# a22.net
KiCad netlist of a schematic drawn in EAGLE
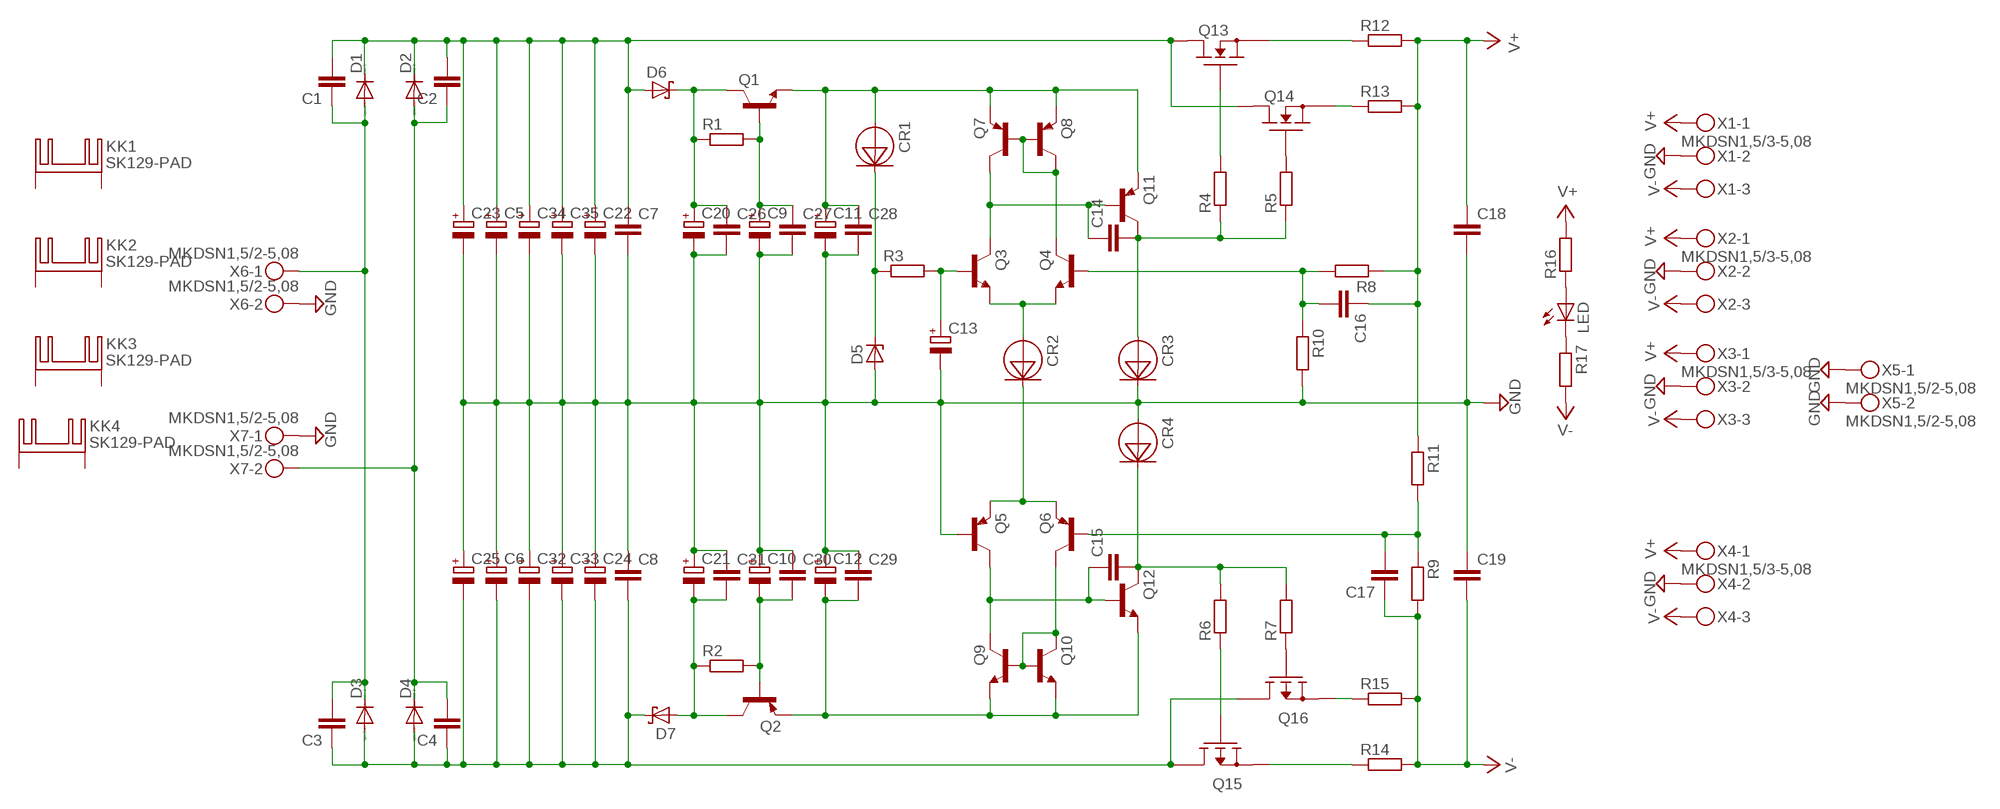
[diagram p0: schematic, sheet 1]

(export (version "E")
  (design (tool "Eeschema 10.0.6"))
  (components
    (comp (ref "C1")
      (value "C-EU025_050-025X075")
      (footprint "eagle-import:C025_050-025X075")
      (libsource (lib "eagle-import") (part "C-EU025_050-025X075"))
    )
    (comp (ref "C2")
      (value "C-EU025_050-025X075")
      (footprint "eagle-import:C025_050-025X075")
      (libsource (lib "eagle-import") (part "C-EU025_050-025X075"))
    )
    (comp (ref "C3")
      (value "C-EU025_050-025X075")
      (footprint "eagle-import:C025_050-025X075")
      (libsource (lib "eagle-import") (part "C-EU025_050-025X075"))
    )
    (comp (ref "C4")
      (value "C-EU025_050-025X075")
      (footprint "eagle-import:C025_050-025X075")
      (libsource (lib "eagle-import") (part "C-EU025_050-025X075"))
    )
    (comp (ref "C5")
      (value "CPOL-EUE10-30")
      (footprint "eagle-import:EB30D")
      (libsource (lib "eagle-import") (part "CPOL-EUE10-30"))
    )
    (comp (ref "C6")
      (value "CPOL-EUE10-30")
      (footprint "eagle-import:EB30D")
      (libsource (lib "eagle-import") (part "CPOL-EUE10-30"))
    )
    (comp (ref "C7")
      (value "C-EU050-075X075")
      (footprint "eagle-import:C050-075X075")
      (libsource (lib "eagle-import") (part "C-EU050-075X075"))
    )
    (comp (ref "C8")
      (value "C-EU050-075X075")
      (footprint "eagle-import:C050-075X075")
      (libsource (lib "eagle-import") (part "C-EU050-075X075"))
    )
    (comp (ref "C9")
      (value "CPOL-EUE5-10.5")
      (footprint "eagle-import:E5-10,5")
      (libsource (lib "eagle-import") (part "CPOL-EUE5-10.5"))
    )
    (comp (ref "C10")
      (value "CPOL-EUE5-10.5")
      (footprint "eagle-import:E5-10,5")
      (libsource (lib "eagle-import") (part "CPOL-EUE5-10.5"))
    )
    (comp (ref "C11")
      (value "CPOL-EUE5-13")
      (footprint "eagle-import:E5-13")
      (libsource (lib "eagle-import") (part "CPOL-EUE5-13"))
    )
    (comp (ref "C12")
      (value "CPOL-EUE5-13")
      (footprint "eagle-import:E5-13")
      (libsource (lib "eagle-import") (part "CPOL-EUE5-13"))
    )
    (comp (ref "C13")
      (value "CPOL-EUE5-10.5")
      (footprint "eagle-import:E5-10,5")
      (libsource (lib "eagle-import") (part "CPOL-EUE5-10.5"))
    )
    (comp (ref "C14")
      (value "C-EU050-075X075")
      (footprint "eagle-import:C050-075X075")
      (libsource (lib "eagle-import") (part "C-EU050-075X075"))
    )
    (comp (ref "C15")
      (value "C-EU050-075X075")
      (footprint "eagle-import:C050-075X075")
      (libsource (lib "eagle-import") (part "C-EU050-075X075"))
    )
    (comp (ref "C16")
      (value "C-EU025_050-045X075")
      (footprint "eagle-import:C025_050-045X075")
      (libsource (lib "eagle-import") (part "C-EU025_050-045X075"))
    )
    (comp (ref "C17")
      (value "C-EU025_050-045X075")
      (footprint "eagle-import:C025_050-045X075")
      (libsource (lib "eagle-import") (part "C-EU025_050-045X075"))
    )
    (comp (ref "C18")
      (value "C-EU050-075X075")
      (footprint "eagle-import:C050-075X075")
      (libsource (lib "eagle-import") (part "C-EU050-075X075"))
    )
    (comp (ref "C19")
      (value "C-EU050-075X075")
      (footprint "eagle-import:C050-075X075")
      (libsource (lib "eagle-import") (part "C-EU050-075X075"))
    )
    (comp (ref "C20")
      (value "CPOL-EUE5-10.5")
      (footprint "eagle-import:E5-10,5")
      (libsource (lib "eagle-import") (part "CPOL-EUE5-10.5"))
    )
    (comp (ref "C21")
      (value "CPOL-EUE5-10.5")
      (footprint "eagle-import:E5-10,5")
      (libsource (lib "eagle-import") (part "CPOL-EUE5-10.5"))
    )
    (comp (ref "C22")
      (value "CPOL-EUE7.5-18")
      (footprint "eagle-import:E7,5-18")
      (libsource (lib "eagle-import") (part "CPOL-EUE7.5-18"))
    )
    (comp (ref "C23")
      (value "CPOL-EUE7.5-18")
      (footprint "eagle-import:E7,5-18")
      (libsource (lib "eagle-import") (part "CPOL-EUE7.5-18"))
    )
    (comp (ref "C24")
      (value "CPOL-EUE7.5-18")
      (footprint "eagle-import:E7,5-18")
      (libsource (lib "eagle-import") (part "CPOL-EUE7.5-18"))
    )
    (comp (ref "C25")
      (value "CPOL-EUE7.5-18")
      (footprint "eagle-import:E7,5-18")
      (libsource (lib "eagle-import") (part "CPOL-EUE7.5-18"))
    )
    (comp (ref "C26")
      (value "C-EU050-035X075")
      (footprint "eagle-import:C050-035X075")
      (libsource (lib "eagle-import") (part "C-EU050-035X075"))
    )
    (comp (ref "C27")
      (value "C-EU050-035X075")
      (footprint "eagle-import:C050-035X075")
      (libsource (lib "eagle-import") (part "C-EU050-035X075"))
    )
    (comp (ref "C28")
      (value "C-EU050-035X075")
      (footprint "eagle-import:C050-035X075")
      (libsource (lib "eagle-import") (part "C-EU050-035X075"))
    )
    (comp (ref "C29")
      (value "C-EU050-035X075")
      (footprint "eagle-import:C050-035X075")
      (libsource (lib "eagle-import") (part "C-EU050-035X075"))
    )
    (comp (ref "C30")
      (value "C-EU050-035X075")
      (footprint "eagle-import:C050-035X075")
      (libsource (lib "eagle-import") (part "C-EU050-035X075"))
    )
    (comp (ref "C31")
      (value "C-EU050-035X075")
      (footprint "eagle-import:C050-035X075")
      (libsource (lib "eagle-import") (part "C-EU050-035X075"))
    )
    (comp (ref "C32")
      (value "CPOL-EUE7.5-18")
      (footprint "eagle-import:E7,5-18")
      (libsource (lib "eagle-import") (part "CPOL-EUE7.5-18"))
    )
    (comp (ref "C33")
      (value "CPOL-EUE7.5-18")
      (footprint "eagle-import:E7,5-18")
      (libsource (lib "eagle-import") (part "CPOL-EUE7.5-18"))
    )
    (comp (ref "C34")
      (value "CPOL-EUE7.5-18")
      (footprint "eagle-import:E7,5-18")
      (libsource (lib "eagle-import") (part "CPOL-EUE7.5-18"))
    )
    (comp (ref "C35")
      (value "CPOL-EUE7.5-18")
      (footprint "eagle-import:E7,5-18")
      (libsource (lib "eagle-import") (part "CPOL-EUE7.5-18"))
    )
    (comp (ref "CR1")
      (value "E-202")
      (footprint "eagle-import:DO-35-3")
      (libsource (lib "eagle-import") (part "E-202"))
    )
    (comp (ref "CR2")
      (value "E-202")
      (footprint "eagle-import:DO-35-3")
      (libsource (lib "eagle-import") (part "E-202"))
    )
    (comp (ref "CR3")
      (value "E-202")
      (footprint "eagle-import:DO-35-3")
      (libsource (lib "eagle-import") (part "E-202"))
    )
    (comp (ref "CR4")
      (value "E-202")
      (footprint "eagle-import:DO-35-3")
      (libsource (lib "eagle-import") (part "E-202"))
    )
    (comp (ref "D1")
      (value "MUR810")
      (footprint "eagle-import:TO220ACS")
      (libsource (lib "eagle-import") (part "MUR810"))
    )
    (comp (ref "D2")
      (value "MUR810")
      (footprint "eagle-import:TO220ACS")
      (libsource (lib "eagle-import") (part "MUR810"))
    )
    (comp (ref "D3")
      (value "MUR810")
      (footprint "eagle-import:TO220ACS")
      (libsource (lib "eagle-import") (part "MUR810"))
    )
    (comp (ref "D4")
      (value "MUR810")
      (footprint "eagle-import:TO220ACS")
      (libsource (lib "eagle-import") (part "MUR810"))
    )
    (comp (ref "D5")
      (value "BZX90")
      (footprint "eagle-import:DO34Z7")
      (libsource (lib "eagle-import") (part "BZX90"))
    )
    (comp (ref "D6")
      (value "1N5819-B")
      (footprint "eagle-import:DO41-7.6")
      (libsource (lib "eagle-import") (part "1N5819-B"))
    )
    (comp (ref "D7")
      (value "1N5819-B")
      (footprint "eagle-import:DO41-7.6")
      (libsource (lib "eagle-import") (part "1N5819-B"))
    )
    (comp (ref "KK1")
      (value "SK129-PAD")
      (footprint "eagle-import:SK129")
      (libsource (lib "eagle-import") (part "SK129-PAD"))
    )
    (comp (ref "KK2")
      (value "SK129-PAD")
      (footprint "eagle-import:SK129")
      (libsource (lib "eagle-import") (part "SK129-PAD"))
    )
    (comp (ref "KK3")
      (value "SK129-PAD")
      (footprint "eagle-import:SK129")
      (libsource (lib "eagle-import") (part "SK129-PAD"))
    )
    (comp (ref "KK4")
      (value "SK129-PAD")
      (footprint "eagle-import:SK129")
      (libsource (lib "eagle-import") (part "SK129-PAD"))
    )
    (comp (ref "LED")
      (value "LED5MM")
      (footprint "eagle-import:LED5MM")
      (libsource (lib "eagle-import") (part "LED5MM"))
    )
    (comp (ref "Q1")
      (value "BC550B")
      (footprint "eagle-import:TO92-EBC")
      (libsource (lib "eagle-import") (part "BC550B"))
    )
    (comp (ref "Q2")
      (value "BC560C")
      (footprint "eagle-import:TO92-EBC")
      (libsource (lib "eagle-import") (part "BC560C"))
    )
    (comp (ref "Q3")
      (value "BC550B")
      (footprint "eagle-import:TO92-EBC")
      (libsource (lib "eagle-import") (part "BC550B"))
    )
    (comp (ref "Q4")
      (value "BC550B")
      (footprint "eagle-import:TO92-EBC")
      (libsource (lib "eagle-import") (part "BC550B"))
    )
    (comp (ref "Q5")
      (value "BC560C")
      (footprint "eagle-import:TO92-EBC")
      (libsource (lib "eagle-import") (part "BC560C"))
    )
    (comp (ref "Q6")
      (value "BC560C")
      (footprint "eagle-import:TO92-EBC")
      (libsource (lib "eagle-import") (part "BC560C"))
    )
    (comp (ref "Q7")
      (value "BC560C")
      (footprint "eagle-import:TO92-EBC")
      (libsource (lib "eagle-import") (part "BC560C"))
    )
    (comp (ref "Q8")
      (value "BC560C")
      (footprint "eagle-import:TO92-EBC")
      (libsource (lib "eagle-import") (part "BC560C"))
    )
    (comp (ref "Q9")
      (value "BC550B")
      (footprint "eagle-import:TO92-EBC")
      (libsource (lib "eagle-import") (part "BC550B"))
    )
    (comp (ref "Q10")
      (value "BC550B")
      (footprint "eagle-import:TO92-EBC")
      (libsource (lib "eagle-import") (part "BC550B"))
    )
    (comp (ref "Q11")
      (value "BC560C")
      (footprint "eagle-import:TO92-EBC")
      (libsource (lib "eagle-import") (part "BC560C"))
    )
    (comp (ref "Q12")
      (value "BC550B")
      (footprint "eagle-import:TO92-EBC")
      (libsource (lib "eagle-import") (part "BC550B"))
    )
    (comp (ref "Q13")
      (value "IRFZ24N")
      (footprint "eagle-import:TO220V")
      (libsource (lib "eagle-import") (part "IRFZ24N"))
    )
    (comp (ref "Q14")
      (value "IRFZ24N")
      (footprint "eagle-import:TO220V")
      (libsource (lib "eagle-import") (part "IRFZ24N"))
    )
    (comp (ref "Q15")
      (value "IRF9Z34N")
      (footprint "eagle-import:TO220V")
      (libsource (lib "eagle-import") (part "IRF9Z34N"))
    )
    (comp (ref "Q16")
      (value "IRF9Z34N")
      (footprint "eagle-import:TO220V")
      (libsource (lib "eagle-import") (part "IRF9Z34N"))
    )
    (comp (ref "R1")
      (value "R-EU_0309/10")
      (footprint "eagle-import:0309_10")
      (libsource (lib "eagle-import") (part "R-EU_0309/10"))
    )
    (comp (ref "R2")
      (value "R-EU_0309/10")
      (footprint "eagle-import:0309_10")
      (libsource (lib "eagle-import") (part "R-EU_0309/10"))
    )
    (comp (ref "R3")
      (value "R-EU_0309/10")
      (footprint "eagle-import:0309_10")
      (libsource (lib "eagle-import") (part "R-EU_0309/10"))
    )
    (comp (ref "R4")
      (value "R-EU_0309/10")
      (footprint "eagle-import:0309_10")
      (libsource (lib "eagle-import") (part "R-EU_0309/10"))
    )
    (comp (ref "R5")
      (value "R-EU_0309/10")
      (footprint "eagle-import:0309_10")
      (libsource (lib "eagle-import") (part "R-EU_0309/10"))
    )
    (comp (ref "R6")
      (value "R-EU_0309/10")
      (footprint "eagle-import:0309_10")
      (libsource (lib "eagle-import") (part "R-EU_0309/10"))
    )
    (comp (ref "R7")
      (value "R-EU_0309/10")
      (footprint "eagle-import:0309_10")
      (libsource (lib "eagle-import") (part "R-EU_0309/10"))
    )
    (comp (ref "R8")
      (value "R-EU_0309/10")
      (footprint "eagle-import:0309_10")
      (libsource (lib "eagle-import") (part "R-EU_0309/10"))
    )
    (comp (ref "R9")
      (value "R-EU_0309/10")
      (footprint "eagle-import:0309_10")
      (libsource (lib "eagle-import") (part "R-EU_0309/10"))
    )
    (comp (ref "R10")
      (value "R-EU_0309/10")
      (footprint "eagle-import:0309_10")
      (libsource (lib "eagle-import") (part "R-EU_0309/10"))
    )
    (comp (ref "R11")
      (value "R-EU_0309/10")
      (footprint "eagle-import:0309_10")
      (libsource (lib "eagle-import") (part "R-EU_0309/10"))
    )
    (comp (ref "R12")
      (value "R-EU_0617/17")
      (footprint "eagle-import:0617_17")
      (libsource (lib "eagle-import") (part "R-EU_0617/17"))
    )
    (comp (ref "R13")
      (value "R-EU_0617/17")
      (footprint "eagle-import:0617_17")
      (libsource (lib "eagle-import") (part "R-EU_0617/17"))
    )
    (comp (ref "R14")
      (value "R-EU_0617/17")
      (footprint "eagle-import:0617_17")
      (libsource (lib "eagle-import") (part "R-EU_0617/17"))
    )
    (comp (ref "R15")
      (value "R-EU_0617/17")
      (footprint "eagle-import:0617_17")
      (libsource (lib "eagle-import") (part "R-EU_0617/17"))
    )
    (comp (ref "R16")
      (value "R-EU_0309/10")
      (footprint "eagle-import:0309_10")
      (libsource (lib "eagle-import") (part "R-EU_0309/10"))
    )
    (comp (ref "R17")
      (value "R-EU_0309/10")
      (footprint "eagle-import:0309_10")
      (libsource (lib "eagle-import") (part "R-EU_0309/10"))
    )
    (comp (ref "X1")
      (value "MKDSN1,5/3-5,08")
      (footprint "eagle-import:MKDSN1,5_3-5,08")
      (libsource (lib "eagle-import") (part "MKDSN1,5/3-5,08"))
    )
    (comp (ref "X2")
      (value "MKDSN1,5/3-5,08")
      (footprint "eagle-import:MKDSN1,5_3-5,08")
      (libsource (lib "eagle-import") (part "MKDSN1,5/3-5,08"))
    )
    (comp (ref "X3")
      (value "MKDSN1,5/3-5,08")
      (footprint "eagle-import:MKDSN1,5_3-5,08")
      (libsource (lib "eagle-import") (part "MKDSN1,5/3-5,08"))
    )
    (comp (ref "X4")
      (value "MKDSN1,5/3-5,08")
      (footprint "eagle-import:MKDSN1,5_3-5,08")
      (libsource (lib "eagle-import") (part "MKDSN1,5/3-5,08"))
    )
    (comp (ref "X5")
      (value "MKDSN1,5/2-5,08")
      (footprint "eagle-import:MKDSN1,5_2-5,08")
      (libsource (lib "eagle-import") (part "MKDSN1,5/2-5,08"))
    )
    (comp (ref "X6")
      (value "MKDSN1,5/2-5,08")
      (footprint "eagle-import:MKDSN1,5_2-5,08")
      (libsource (lib "eagle-import") (part "MKDSN1,5/2-5,08"))
    )
    (comp (ref "X7")
      (value "MKDSN1,5/2-5,08")
      (footprint "eagle-import:MKDSN1,5_2-5,08")
      (libsource (lib "eagle-import") (part "MKDSN1,5/2-5,08"))
    )
  )
  (nets
    (net (code "1") (name "GND") (class "Default")
      (node (ref "C10") (pin "+") (pinfunction "+_+") (pintype "passive"))
      (node (ref "C11") (pin "-") (pinfunction "-_-") (pintype "passive"))
      (node (ref "C12") (pin "+") (pinfunction "+_+") (pintype "passive"))
      (node (ref "C13") (pin "-") (pinfunction "-_-") (pintype "passive"))
      (node (ref "C18") (pin "2") (pinfunction "2_2") (pintype "passive"))
      (node (ref "C19") (pin "1") (pinfunction "1_1") (pintype "passive"))
      (node (ref "C20") (pin "-") (pinfunction "-_-") (pintype "passive"))
      (node (ref "C21") (pin "+") (pinfunction "+_+") (pintype "passive"))
      (node (ref "C22") (pin "-") (pinfunction "-_-") (pintype "passive"))
      (node (ref "C23") (pin "-") (pinfunction "-_-") (pintype "passive"))
      (node (ref "C24") (pin "+") (pinfunction "+_+") (pintype "passive"))
      (node (ref "C25") (pin "+") (pinfunction "+_+") (pintype "passive"))
      (node (ref "C26") (pin "2") (pinfunction "2_2") (pintype "passive"))
      (node (ref "C27") (pin "2") (pinfunction "2_2") (pintype "passive"))
      (node (ref "C28") (pin "2") (pinfunction "2_2") (pintype "passive"))
      (node (ref "C29") (pin "1") (pinfunction "1_1") (pintype "passive"))
      (node (ref "C30") (pin "1") (pinfunction "1_1") (pintype "passive"))
      (node (ref "C31") (pin "1") (pinfunction "1_1") (pintype "passive"))
      (node (ref "C32") (pin "+") (pinfunction "+_+") (pintype "passive"))
      (node (ref "C33") (pin "+") (pinfunction "+_+") (pintype "passive"))
      (node (ref "C34") (pin "-") (pinfunction "-_-") (pintype "passive"))
      (node (ref "C35") (pin "-") (pinfunction "-_-") (pintype "passive"))
      (node (ref "C5") (pin "-") (pinfunction "-_-") (pintype "passive"))
      (node (ref "C6") (pin "+") (pinfunction "+_+") (pintype "passive"))
      (node (ref "C7") (pin "2") (pinfunction "2_2") (pintype "passive"))
      (node (ref "C8") (pin "1") (pinfunction "1_1") (pintype "passive"))
      (node (ref "C9") (pin "-") (pinfunction "-_-") (pintype "passive"))
      (node (ref "CR3") (pin "1") (pinfunction "CATHODE_1") (pintype "passive"))
      (node (ref "CR3") (pin "2") (pinfunction "CATHODE_2") (pintype "passive"))
      (node (ref "CR3") (pin "CATHODE") (pinfunction "CATHODE_CATHODE") (pintype "passive"))
      (node (ref "CR4") (pin "ANODE") (pinfunction "ANODE_ANODE") (pintype "passive"))
      (node (ref "D5") (pin "A") (pinfunction "A_A") (pintype "passive"))
      (node (ref "Q5") (pin "B") (pinfunction "B_B") (pintype "passive"))
      (node (ref "R10") (pin "2") (pinfunction "2_2") (pintype "passive"))
      (node (ref "X1") (pin "2") (pinfunction "KL_2") (pintype "passive"))
      (node (ref "X2") (pin "2") (pinfunction "KL_2") (pintype "passive"))
      (node (ref "X3") (pin "2") (pinfunction "KL_2") (pintype "passive"))
      (node (ref "X4") (pin "2") (pinfunction "KL_2") (pintype "passive"))
      (node (ref "X5") (pin "1") (pinfunction "KL_1") (pintype "passive"))
      (node (ref "X5") (pin "2") (pinfunction "KL_2") (pintype "passive"))
      (node (ref "X6") (pin "2") (pinfunction "KL_2") (pintype "passive"))
      (node (ref "X7") (pin "1") (pinfunction "KL_1") (pintype "passive"))
    )
    (net (code "2") (name "Net-(C10-Pad-)") (class "Default")
      (node (ref "C10") (pin "-") (pinfunction "-_-") (pintype "passive"))
      (node (ref "C30") (pin "2") (pinfunction "2_2") (pintype "passive"))
      (node (ref "Q2") (pin "B") (pinfunction "B_B") (pintype "passive"))
      (node (ref "R2") (pin "2") (pinfunction "2_2") (pintype "passive"))
    )
    (net (code "3") (name "Net-(C11-Pad+)") (class "Default")
      (node (ref "C11") (pin "+") (pinfunction "+_+") (pintype "passive"))
      (node (ref "C28") (pin "1") (pinfunction "1_1") (pintype "passive"))
      (node (ref "CR1") (pin "ANODE") (pinfunction "ANODE_ANODE") (pintype "passive"))
      (node (ref "Q1") (pin "E") (pinfunction "E_E") (pintype "passive"))
      (node (ref "Q11") (pin "E") (pinfunction "E_E") (pintype "passive"))
      (node (ref "Q7") (pin "E") (pinfunction "E_E") (pintype "passive"))
      (node (ref "Q8") (pin "E") (pinfunction "E_E") (pintype "passive"))
    )
    (net (code "4") (name "Net-(C12-Pad-)") (class "Default")
      (node (ref "C12") (pin "-") (pinfunction "-_-") (pintype "passive"))
      (node (ref "C29") (pin "2") (pinfunction "2_2") (pintype "passive"))
      (node (ref "Q10") (pin "E") (pinfunction "E_E") (pintype "passive"))
      (node (ref "Q12") (pin "E") (pinfunction "E_E") (pintype "passive"))
      (node (ref "Q2") (pin "E") (pinfunction "E_E") (pintype "passive"))
      (node (ref "Q9") (pin "E") (pinfunction "E_E") (pintype "passive"))
    )
    (net (code "5") (name "Net-(C13-Pad+)") (class "Default")
      (node (ref "C13") (pin "+") (pinfunction "+_+") (pintype "passive"))
      (node (ref "Q3") (pin "B") (pinfunction "B_B") (pintype "passive"))
      (node (ref "R3") (pin "2") (pinfunction "2_2") (pintype "passive"))
    )
    (net (code "6") (name "Net-(C14-Pad1)") (class "Default")
      (node (ref "C14") (pin "1") (pinfunction "1_1") (pintype "passive"))
      (node (ref "Q11") (pin "B") (pinfunction "B_B") (pintype "passive"))
      (node (ref "Q3") (pin "C") (pinfunction "C_C") (pintype "passive"))
      (node (ref "Q7") (pin "C") (pinfunction "C_C") (pintype "passive"))
    )
    (net (code "7") (name "Net-(C14-Pad2)") (class "Default")
      (node (ref "C14") (pin "2") (pinfunction "2_2") (pintype "passive"))
      (node (ref "CR3") (pin "ANODE") (pinfunction "ANODE_ANODE") (pintype "passive"))
      (node (ref "Q11") (pin "C") (pinfunction "C_C") (pintype "passive"))
      (node (ref "R4") (pin "1") (pinfunction "1_1") (pintype "passive"))
      (node (ref "R5") (pin "1") (pinfunction "1_1") (pintype "passive"))
    )
    (net (code "8") (name "Net-(C15-Pad1)") (class "Default")
      (node (ref "C15") (pin "1") (pinfunction "1_1") (pintype "passive"))
      (node (ref "Q12") (pin "B") (pinfunction "B_B") (pintype "passive"))
      (node (ref "Q5") (pin "C") (pinfunction "C_C") (pintype "passive"))
      (node (ref "Q9") (pin "C") (pinfunction "C_C") (pintype "passive"))
    )
    (net (code "9") (name "Net-(C15-Pad2)") (class "Default")
      (node (ref "C15") (pin "2") (pinfunction "2_2") (pintype "passive"))
      (node (ref "CR4") (pin "1") (pinfunction "CATHODE_1") (pintype "passive"))
      (node (ref "CR4") (pin "2") (pinfunction "CATHODE_2") (pintype "passive"))
      (node (ref "CR4") (pin "CATHODE") (pinfunction "CATHODE_CATHODE") (pintype "passive"))
      (node (ref "Q12") (pin "C") (pinfunction "C_C") (pintype "passive"))
      (node (ref "R6") (pin "2") (pinfunction "2_2") (pintype "passive"))
      (node (ref "R7") (pin "2") (pinfunction "2_2") (pintype "passive"))
    )
    (net (code "10") (name "Net-(C16-2-Pad3)") (class "Default")
      (node (ref "C16") (pin "2") (pinfunction "2_2") (pintype "passive"))
      (node (ref "C16") (pin "3") (pinfunction "2_3") (pintype "passive"))
      (node (ref "Q4") (pin "B") (pinfunction "B_B") (pintype "passive"))
      (node (ref "R10") (pin "1") (pinfunction "1_1") (pintype "passive"))
      (node (ref "R8") (pin "2") (pinfunction "2_2") (pintype "passive"))
    )
    (net (code "11") (name "Net-(C17-2-Pad3)") (class "Default")
      (node (ref "C17") (pin "2") (pinfunction "2_2") (pintype "passive"))
      (node (ref "C17") (pin "3") (pinfunction "2_3") (pintype "passive"))
      (node (ref "Q6") (pin "B") (pinfunction "B_B") (pintype "passive"))
      (node (ref "R11") (pin "2") (pinfunction "2_2") (pintype "passive"))
      (node (ref "R9") (pin "1") (pinfunction "1_1") (pintype "passive"))
    )
    (net (code "12") (name "Net-(C20-Pad+)") (class "Default")
      (node (ref "C20") (pin "+") (pinfunction "+_+") (pintype "passive"))
      (node (ref "C26") (pin "1") (pinfunction "1_1") (pintype "passive"))
      (node (ref "D6") (pin "C") (pinfunction "C_C") (pintype "passive"))
      (node (ref "Q1") (pin "C") (pinfunction "C_C") (pintype "passive"))
      (node (ref "R1") (pin "1") (pinfunction "1_1") (pintype "passive"))
    )
    (net (code "13") (name "Net-(C21-Pad-)") (class "Default")
      (node (ref "C21") (pin "-") (pinfunction "-_-") (pintype "passive"))
      (node (ref "C31") (pin "2") (pinfunction "2_2") (pintype "passive"))
      (node (ref "D7") (pin "A") (pinfunction "A_A") (pintype "passive"))
      (node (ref "Q2") (pin "C") (pinfunction "C_C") (pintype "passive"))
      (node (ref "R2") (pin "1") (pinfunction "1_1") (pintype "passive"))
    )
    (net (code "14") (name "Net-(C27-Pad1)") (class "Default")
      (node (ref "C27") (pin "1") (pinfunction "1_1") (pintype "passive"))
      (node (ref "C9") (pin "+") (pinfunction "+_+") (pintype "passive"))
      (node (ref "Q1") (pin "B") (pinfunction "B_B") (pintype "passive"))
      (node (ref "R1") (pin "2") (pinfunction "2_2") (pintype "passive"))
    )
    (net (code "15") (name "Net-(CR1-CATHODE-Pad1)") (class "Default")
      (node (ref "CR1") (pin "1") (pinfunction "CATHODE_1") (pintype "passive"))
      (node (ref "CR1") (pin "2") (pinfunction "CATHODE_2") (pintype "passive"))
      (node (ref "CR1") (pin "CATHODE") (pinfunction "CATHODE_CATHODE") (pintype "passive"))
      (node (ref "D5") (pin "C") (pinfunction "C_C") (pintype "passive"))
      (node (ref "R3") (pin "1") (pinfunction "1_1") (pintype "passive"))
    )
    (net (code "16") (name "Net-(CR2-CATHODE-Pad1)") (class "Default")
      (node (ref "CR2") (pin "1") (pinfunction "CATHODE_1") (pintype "passive"))
      (node (ref "CR2") (pin "2") (pinfunction "CATHODE_2") (pintype "passive"))
      (node (ref "CR2") (pin "CATHODE") (pinfunction "CATHODE_CATHODE") (pintype "passive"))
      (node (ref "Q5") (pin "E") (pinfunction "E_E") (pintype "passive"))
      (node (ref "Q6") (pin "E") (pinfunction "E_E") (pintype "passive"))
    )
    (net (code "17") (name "Net-(CR2-PadANODE)") (class "Default")
      (node (ref "CR2") (pin "ANODE") (pinfunction "ANODE_ANODE") (pintype "passive"))
      (node (ref "Q3") (pin "E") (pinfunction "E_E") (pintype "passive"))
      (node (ref "Q4") (pin "E") (pinfunction "E_E") (pintype "passive"))
    )
    (net (code "18") (name "Net-(LED-C)") (class "Default")
      (node (ref "LED") (pin "K") (pinfunction "C_K") (pintype "passive"))
      (node (ref "R17") (pin "1") (pinfunction "1_1") (pintype "passive"))
    )
    (net (code "19") (name "Net-(LED-PadA)") (class "Default")
      (node (ref "LED") (pin "A") (pinfunction "A_A") (pintype "passive"))
      (node (ref "R16") (pin "1") (pinfunction "1_1") (pintype "passive"))
    )
    (net (code "20") (name "Net-(Q4-PadC)") (class "Default")
      (node (ref "Q4") (pin "C") (pinfunction "C_C") (pintype "passive"))
      (node (ref "Q7") (pin "B") (pinfunction "B_B") (pintype "passive"))
      (node (ref "Q8") (pin "B") (pinfunction "B_B") (pintype "passive"))
      (node (ref "Q8") (pin "C") (pinfunction "C_C") (pintype "passive"))
    )
    (net (code "21") (name "Net-(Q10-PadB)") (class "Default")
      (node (ref "Q10") (pin "B") (pinfunction "B_B") (pintype "passive"))
      (node (ref "Q10") (pin "C") (pinfunction "C_C") (pintype "passive"))
      (node (ref "Q6") (pin "C") (pinfunction "C_C") (pintype "passive"))
      (node (ref "Q9") (pin "B") (pinfunction "B_B") (pintype "passive"))
    )
    (net (code "22") (name "Net-(Q13-D)") (class "Default")
      (node (ref "C1") (pin "2") (pinfunction "2_2") (pintype "passive"))
      (node (ref "C1") (pin "3") (pinfunction "2_3") (pintype "passive"))
      (node (ref "C2") (pin "2") (pinfunction "2_2") (pintype "passive"))
      (node (ref "C2") (pin "3") (pinfunction "2_3") (pintype "passive"))
      (node (ref "C22") (pin "+") (pinfunction "+_+") (pintype "passive"))
      (node (ref "C23") (pin "+") (pinfunction "+_+") (pintype "passive"))
      (node (ref "C34") (pin "+") (pinfunction "+_+") (pintype "passive"))
      (node (ref "C35") (pin "+") (pinfunction "+_+") (pintype "passive"))
      (node (ref "C5") (pin "+") (pinfunction "+_+") (pintype "passive"))
      (node (ref "C7") (pin "1") (pinfunction "1_1") (pintype "passive"))
      (node (ref "D1") (pin "C") (pinfunction "C_C") (pintype "passive"))
      (node (ref "D2") (pin "C") (pinfunction "C_C") (pintype "passive"))
      (node (ref "D6") (pin "A") (pinfunction "A_A") (pintype "passive"))
      (node (ref "Q13") (pin "2") (pinfunction "D_2") (pintype "passive"))
      (node (ref "Q14") (pin "2") (pinfunction "D_2") (pintype "passive"))
    )
    (net (code "23") (name "Net-(Q13-G)") (class "Default")
      (node (ref "Q13") (pin "1") (pinfunction "G_1") (pintype "passive"))
      (node (ref "R4") (pin "2") (pinfunction "2_2") (pintype "passive"))
    )
    (net (code "24") (name "Net-(Q13-S)") (class "Default")
      (node (ref "Q13") (pin "3") (pinfunction "S_3") (pintype "passive"))
      (node (ref "R12") (pin "1") (pinfunction "1_1") (pintype "passive"))
    )
    (net (code "25") (name "Net-(Q14-G)") (class "Default")
      (node (ref "Q14") (pin "1") (pinfunction "G_1") (pintype "passive"))
      (node (ref "R5") (pin "2") (pinfunction "2_2") (pintype "passive"))
    )
    (net (code "26") (name "Net-(Q14-S)") (class "Default")
      (node (ref "Q14") (pin "3") (pinfunction "S_3") (pintype "passive"))
      (node (ref "R13") (pin "1") (pinfunction "1_1") (pintype "passive"))
    )
    (net (code "27") (name "Net-(Q15-D)") (class "Default")
      (node (ref "C24") (pin "-") (pinfunction "-_-") (pintype "passive"))
      (node (ref "C25") (pin "-") (pinfunction "-_-") (pintype "passive"))
      (node (ref "C3") (pin "1") (pinfunction "1_1") (pintype "passive"))
      (node (ref "C32") (pin "-") (pinfunction "-_-") (pintype "passive"))
      (node (ref "C33") (pin "-") (pinfunction "-_-") (pintype "passive"))
      (node (ref "C4") (pin "1") (pinfunction "1_1") (pintype "passive"))
      (node (ref "C6") (pin "-") (pinfunction "-_-") (pintype "passive"))
      (node (ref "C8") (pin "2") (pinfunction "2_2") (pintype "passive"))
      (node (ref "D3") (pin "A") (pinfunction "A_A") (pintype "passive"))
      (node (ref "D4") (pin "A") (pinfunction "A_A") (pintype "passive"))
      (node (ref "D7") (pin "C") (pinfunction "C_C") (pintype "passive"))
      (node (ref "Q15") (pin "2") (pinfunction "D_2") (pintype "passive"))
      (node (ref "Q16") (pin "2") (pinfunction "D_2") (pintype "passive"))
    )
    (net (code "28") (name "Net-(Q15-G)") (class "Default")
      (node (ref "Q15") (pin "1") (pinfunction "G_1") (pintype "passive"))
      (node (ref "R6") (pin "1") (pinfunction "1_1") (pintype "passive"))
    )
    (net (code "29") (name "Net-(Q15-S)") (class "Default")
      (node (ref "Q15") (pin "3") (pinfunction "S_3") (pintype "passive"))
      (node (ref "R14") (pin "1") (pinfunction "1_1") (pintype "passive"))
    )
    (net (code "30") (name "Net-(Q16-G)") (class "Default")
      (node (ref "Q16") (pin "1") (pinfunction "G_1") (pintype "passive"))
      (node (ref "R7") (pin "1") (pinfunction "1_1") (pintype "passive"))
    )
    (net (code "31") (name "Net-(Q16-S)") (class "Default")
      (node (ref "Q16") (pin "3") (pinfunction "S_3") (pintype "passive"))
      (node (ref "R15") (pin "1") (pinfunction "1_1") (pintype "passive"))
    )
    (net (code "32") (name "Net-(X6A-KL)") (class "Default")
      (node (ref "C1") (pin "1") (pinfunction "1_1") (pintype "passive"))
      (node (ref "C3") (pin "2") (pinfunction "2_2") (pintype "passive"))
      (node (ref "C3") (pin "3") (pinfunction "2_3") (pintype "passive"))
      (node (ref "D1") (pin "A") (pinfunction "A_A") (pintype "passive"))
      (node (ref "D3") (pin "C") (pinfunction "C_C") (pintype "passive"))
      (node (ref "X6") (pin "1") (pinfunction "KL_1") (pintype "passive"))
    )
    (net (code "33") (name "Net-(X7B-KL)") (class "Default")
      (node (ref "C2") (pin "1") (pinfunction "1_1") (pintype "passive"))
      (node (ref "C4") (pin "2") (pinfunction "2_2") (pintype "passive"))
      (node (ref "C4") (pin "3") (pinfunction "2_3") (pintype "passive"))
      (node (ref "D2") (pin "A") (pinfunction "A_A") (pintype "passive"))
      (node (ref "D4") (pin "C") (pinfunction "C_C") (pintype "passive"))
      (node (ref "X7") (pin "2") (pinfunction "KL_2") (pintype "passive"))
    )
    (net (code "34") (name "V+") (class "Default")
      (node (ref "C16") (pin "1") (pinfunction "1_1") (pintype "passive"))
      (node (ref "C18") (pin "1") (pinfunction "1_1") (pintype "passive"))
      (node (ref "R11") (pin "1") (pinfunction "1_1") (pintype "passive"))
      (node (ref "R12") (pin "2") (pinfunction "2_2") (pintype "passive"))
      (node (ref "R13") (pin "2") (pinfunction "2_2") (pintype "passive"))
      (node (ref "R16") (pin "2") (pinfunction "2_2") (pintype "passive"))
      (node (ref "R8") (pin "1") (pinfunction "1_1") (pintype "passive"))
      (node (ref "X1") (pin "1") (pinfunction "KL_1") (pintype "passive"))
      (node (ref "X2") (pin "1") (pinfunction "KL_1") (pintype "passive"))
      (node (ref "X3") (pin "1") (pinfunction "KL_1") (pintype "passive"))
      (node (ref "X4") (pin "1") (pinfunction "KL_1") (pintype "passive"))
    )
    (net (code "35") (name "V-") (class "Default")
      (node (ref "C17") (pin "1") (pinfunction "1_1") (pintype "passive"))
      (node (ref "C19") (pin "2") (pinfunction "2_2") (pintype "passive"))
      (node (ref "R14") (pin "2") (pinfunction "2_2") (pintype "passive"))
      (node (ref "R15") (pin "2") (pinfunction "2_2") (pintype "passive"))
      (node (ref "R17") (pin "2") (pinfunction "2_2") (pintype "passive"))
      (node (ref "R9") (pin "2") (pinfunction "2_2") (pintype "passive"))
      (node (ref "X1") (pin "3") (pinfunction "KL_3") (pintype "passive"))
      (node (ref "X2") (pin "3") (pinfunction "KL_3") (pintype "passive"))
      (node (ref "X3") (pin "3") (pinfunction "KL_3") (pintype "passive"))
      (node (ref "X4") (pin "3") (pinfunction "KL_3") (pintype "passive"))
    )
    (net (code "36") (name "unconnected-(KK1-K-PadA2,5)") (class "Default")
      (node (ref "KK1") (pin "A2,5") (pinfunction "K_A2,5") (pintype "passive"))
    )
    (net (code "37") (name "unconnected-(KK1-K-PadB2,5)") (class "Default")
      (node (ref "KK1") (pin "B2,5") (pinfunction "K_B2,5") (pintype "passive"))
    )
    (net (code "38") (name "unconnected-(KK2-K-PadA2,5)") (class "Default")
      (node (ref "KK2") (pin "A2,5") (pinfunction "K_A2,5") (pintype "passive"))
    )
    (net (code "39") (name "unconnected-(KK2-K-PadB2,5)") (class "Default")
      (node (ref "KK2") (pin "B2,5") (pinfunction "K_B2,5") (pintype "passive"))
    )
    (net (code "40") (name "unconnected-(KK3-K-PadA2,5)") (class "Default")
      (node (ref "KK3") (pin "A2,5") (pinfunction "K_A2,5") (pintype "passive"))
    )
    (net (code "41") (name "unconnected-(KK3-K-PadB2,5)") (class "Default")
      (node (ref "KK3") (pin "B2,5") (pinfunction "K_B2,5") (pintype "passive"))
    )
    (net (code "42") (name "unconnected-(KK4-K-PadA2,5)") (class "Default")
      (node (ref "KK4") (pin "A2,5") (pinfunction "K_A2,5") (pintype "passive"))
    )
    (net (code "43") (name "unconnected-(KK4-K-PadB2,5)") (class "Default")
      (node (ref "KK4") (pin "B2,5") (pinfunction "K_B2,5") (pintype "passive"))
    )
  )
)
